# buffered-mult.net
KiCad netlist of a schematic drawn in EAGLE
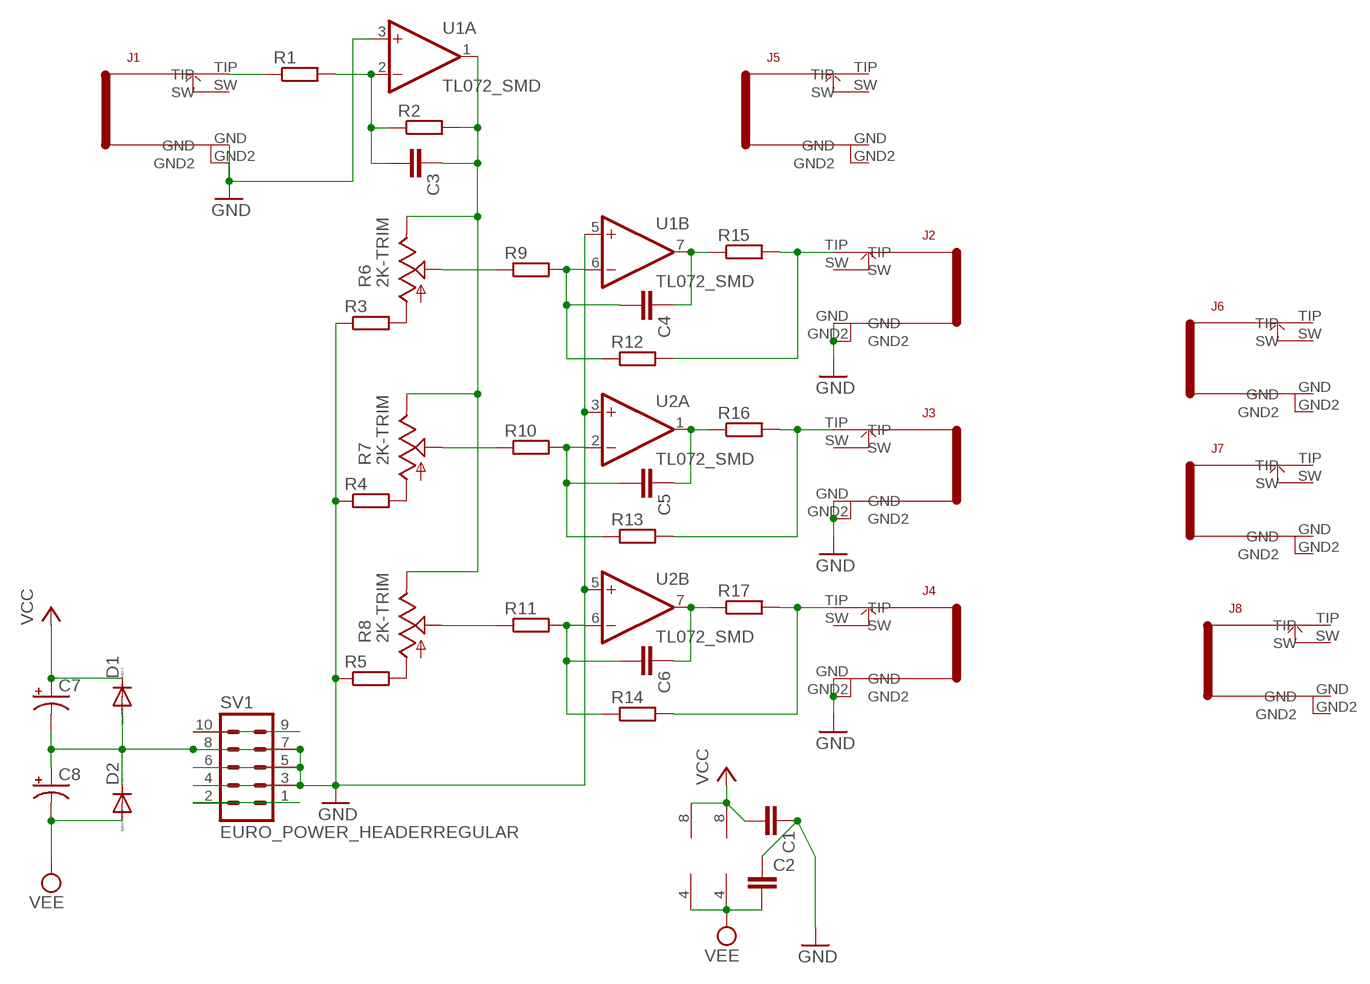
[diagram p0: schematic, sheet 1]

(export (version "E")
  (design (tool "Eeschema 10.0.6"))
  (components
    (comp (ref "C1")
      (value "C-EUC0603")
      (footprint "eagle-import:C0603")
      (libsource (lib "eagle-import") (part "C-EUC0603"))
    )
    (comp (ref "C2")
      (value "C-EUC0603")
      (footprint "eagle-import:C0603")
      (libsource (lib "eagle-import") (part "C-EUC0603"))
    )
    (comp (ref "C3")
      (value "C-EUC0603")
      (footprint "eagle-import:C0603")
      (libsource (lib "eagle-import") (part "C-EUC0603"))
    )
    (comp (ref "C4")
      (value "C-EUC0603")
      (footprint "eagle-import:C0603")
      (libsource (lib "eagle-import") (part "C-EUC0603"))
    )
    (comp (ref "C5")
      (value "C-EUC0603")
      (footprint "eagle-import:C0603")
      (libsource (lib "eagle-import") (part "C-EUC0603"))
    )
    (comp (ref "C6")
      (value "C-EUC0603")
      (footprint "eagle-import:C0603")
      (libsource (lib "eagle-import") (part "C-EUC0603"))
    )
    (comp (ref "C7")
      (value "CPOL-USD")
      (footprint "eagle-import:PANASONIC_D")
      (libsource (lib "eagle-import") (part "CPOL-USD"))
    )
    (comp (ref "C8")
      (value "CPOL-USD")
      (footprint "eagle-import:PANASONIC_D")
      (libsource (lib "eagle-import") (part "CPOL-USD"))
    )
    (comp (ref "D1")
      (value "DIODE-SOD123")
      (footprint "eagle-import:SOD123")
      (libsource (lib "eagle-import") (part "DIODE-SOD123"))
    )
    (comp (ref "D2")
      (value "DIODE-SOD123")
      (footprint "eagle-import:SOD123")
      (libsource (lib "eagle-import") (part "DIODE-SOD123"))
    )
    (comp (ref "J1")
      (value "WQP_PJ_301BM")
      (footprint "eagle-import:WQP_PJ_301BM")
      (libsource (lib "eagle-import") (part "WQP_PJ_301BM"))
    )
    (comp (ref "J2")
      (value "WQP_PJ_301BM")
      (footprint "eagle-import:WQP_PJ_301BM")
      (libsource (lib "eagle-import") (part "WQP_PJ_301BM"))
    )
    (comp (ref "J3")
      (value "WQP_PJ_301BM")
      (footprint "eagle-import:WQP_PJ_301BM")
      (libsource (lib "eagle-import") (part "WQP_PJ_301BM"))
    )
    (comp (ref "J4")
      (value "WQP_PJ_301BM")
      (footprint "eagle-import:WQP_PJ_301BM")
      (libsource (lib "eagle-import") (part "WQP_PJ_301BM"))
    )
    (comp (ref "J5")
      (value "WQP_PJ_301BM")
      (footprint "eagle-import:WQP_PJ_301BM")
      (libsource (lib "eagle-import") (part "WQP_PJ_301BM"))
    )
    (comp (ref "J6")
      (value "WQP_PJ_301BM")
      (footprint "eagle-import:WQP_PJ_301BM")
      (libsource (lib "eagle-import") (part "WQP_PJ_301BM"))
    )
    (comp (ref "J7")
      (value "WQP_PJ_301BM")
      (footprint "eagle-import:WQP_PJ_301BM")
      (libsource (lib "eagle-import") (part "WQP_PJ_301BM"))
    )
    (comp (ref "J8")
      (value "WQP_PJ_301BM")
      (footprint "eagle-import:WQP_PJ_301BM")
      (libsource (lib "eagle-import") (part "WQP_PJ_301BM"))
    )
    (comp (ref "R1")
      (value "R-EU_R0603")
      (footprint "eagle-import:R0603")
      (libsource (lib "eagle-import") (part "R-EU_R0603"))
    )
    (comp (ref "R2")
      (value "R-EU_R0603")
      (footprint "eagle-import:R0603")
      (libsource (lib "eagle-import") (part "R-EU_R0603"))
    )
    (comp (ref "R3")
      (value "R-EU_R0603")
      (footprint "eagle-import:R0603")
      (libsource (lib "eagle-import") (part "R-EU_R0603"))
    )
    (comp (ref "R4")
      (value "R-EU_R0603")
      (footprint "eagle-import:R0603")
      (libsource (lib "eagle-import") (part "R-EU_R0603"))
    )
    (comp (ref "R5")
      (value "R-EU_R0603")
      (footprint "eagle-import:R0603")
      (libsource (lib "eagle-import") (part "R-EU_R0603"))
    )
    (comp (ref "R6")
      (value "2K-TRIM")
      (footprint "eagle-import:BOURNS_TRIM_3303X3_SMD")
      (libsource (lib "eagle-import") (part "BOURNS_TRIM_3303X3_SMD"))
    )
    (comp (ref "R7")
      (value "2K-TRIM")
      (footprint "eagle-import:BOURNS_TRIM_3303X3_SMD")
      (libsource (lib "eagle-import") (part "BOURNS_TRIM_3303X3_SMD"))
    )
    (comp (ref "R8")
      (value "2K-TRIM")
      (footprint "eagle-import:BOURNS_TRIM_3303X3_SMD")
      (libsource (lib "eagle-import") (part "BOURNS_TRIM_3303X3_SMD"))
    )
    (comp (ref "R9")
      (value "R-EU_R0603")
      (footprint "eagle-import:R0603")
      (libsource (lib "eagle-import") (part "R-EU_R0603"))
    )
    (comp (ref "R10")
      (value "R-EU_R0603")
      (footprint "eagle-import:R0603")
      (libsource (lib "eagle-import") (part "R-EU_R0603"))
    )
    (comp (ref "R11")
      (value "R-EU_R0603")
      (footprint "eagle-import:R0603")
      (libsource (lib "eagle-import") (part "R-EU_R0603"))
    )
    (comp (ref "R12")
      (value "R-EU_R0603")
      (footprint "eagle-import:R0603")
      (libsource (lib "eagle-import") (part "R-EU_R0603"))
    )
    (comp (ref "R13")
      (value "R-EU_R0603")
      (footprint "eagle-import:R0603")
      (libsource (lib "eagle-import") (part "R-EU_R0603"))
    )
    (comp (ref "R14")
      (value "R-EU_R0603")
      (footprint "eagle-import:R0603")
      (libsource (lib "eagle-import") (part "R-EU_R0603"))
    )
    (comp (ref "R15")
      (value "R-EU_R0603")
      (footprint "eagle-import:R0603")
      (libsource (lib "eagle-import") (part "R-EU_R0603"))
    )
    (comp (ref "R16")
      (value "R-EU_R0603")
      (footprint "eagle-import:R0603")
      (libsource (lib "eagle-import") (part "R-EU_R0603"))
    )
    (comp (ref "R17")
      (value "R-EU_R0603")
      (footprint "eagle-import:R0603")
      (libsource (lib "eagle-import") (part "R-EU_R0603"))
    )
    (comp (ref "SV1")
      (value "EURO_POWER_HEADERREGULAR")
      (footprint "eagle-import:EURO_POWER_HEADER")
      (libsource (lib "eagle-import") (part "EURO_POWER_HEADERREGULAR"))
    )
    (comp (ref "U1")
      (value "TL072_SMD")
      (footprint "eagle-import:SO08")
      (libsource (lib "eagle-import") (part "TL072_SMD"))
    )
    (comp (ref "U2")
      (value "TL072_SMD")
      (footprint "eagle-import:SO08")
      (libsource (lib "eagle-import") (part "TL072_SMD"))
    )
  )
  (nets
    (net (code "1") (name "GND") (class "Default")
      (node (ref "C1") (pin "1") (pinfunction "1_1") (pintype "passive"))
      (node (ref "C2") (pin "1") (pinfunction "1_1") (pintype "passive"))
      (node (ref "C7") (pin "-") (pinfunction "-_-") (pintype "passive"))
      (node (ref "C8") (pin "+") (pinfunction "+_+") (pintype "passive"))
      (node (ref "D1") (pin "A") (pinfunction "A_A") (pintype "passive"))
      (node (ref "D2") (pin "C") (pinfunction "C_C") (pintype "passive"))
      (node (ref "J1") (pin "GND") (pinfunction "GND_GND") (pintype "passive"))
      (node (ref "J1") (pin "GND2") (pinfunction "GND2_GND2") (pintype "passive"))
      (node (ref "J2") (pin "GND") (pinfunction "GND_GND") (pintype "passive"))
      (node (ref "J2") (pin "GND2") (pinfunction "GND2_GND2") (pintype "passive"))
      (node (ref "J3") (pin "GND") (pinfunction "GND_GND") (pintype "passive"))
      (node (ref "J3") (pin "GND2") (pinfunction "GND2_GND2") (pintype "passive"))
      (node (ref "J4") (pin "GND") (pinfunction "GND_GND") (pintype "passive"))
      (node (ref "J4") (pin "GND2") (pinfunction "GND2_GND2") (pintype "passive"))
      (node (ref "R3") (pin "1") (pinfunction "1_1") (pintype "passive"))
      (node (ref "R4") (pin "1") (pinfunction "1_1") (pintype "passive"))
      (node (ref "R5") (pin "1") (pinfunction "1_1") (pintype "passive"))
      (node (ref "SV1") (pin "3") (pinfunction "3_3") (pintype "passive"))
      (node (ref "SV1") (pin "4") (pinfunction "4_4") (pintype "passive"))
      (node (ref "SV1") (pin "5") (pinfunction "5_5") (pintype "passive"))
      (node (ref "SV1") (pin "6") (pinfunction "6_6") (pintype "passive"))
      (node (ref "SV1") (pin "7") (pinfunction "7_7") (pintype "passive"))
      (node (ref "SV1") (pin "8") (pinfunction "8_8") (pintype "passive"))
      (node (ref "U1") (pin "3") (pinfunction "+IN_3") (pintype "input"))
      (node (ref "U1") (pin "5") (pinfunction "+IN_5") (pintype "input"))
      (node (ref "U2") (pin "3") (pinfunction "+IN_3") (pintype "input"))
      (node (ref "U2") (pin "5") (pinfunction "+IN_5") (pintype "input"))
    )
    (net (code "2") (name "Net-(J1-PadTIP)") (class "Default")
      (node (ref "J1") (pin "TIP") (pinfunction "TIP_TIP") (pintype "passive"))
      (node (ref "R1") (pin "1") (pinfunction "1_1") (pintype "passive"))
    )
    (net (code "3") (name "Net-(J2-PadTIP)") (class "Default")
      (node (ref "J2") (pin "TIP") (pinfunction "TIP_TIP") (pintype "passive"))
      (node (ref "R12") (pin "2") (pinfunction "2_2") (pintype "passive"))
      (node (ref "R15") (pin "2") (pinfunction "2_2") (pintype "passive"))
    )
    (net (code "4") (name "Net-(J3-PadTIP)") (class "Default")
      (node (ref "J3") (pin "TIP") (pinfunction "TIP_TIP") (pintype "passive"))
      (node (ref "R13") (pin "2") (pinfunction "2_2") (pintype "passive"))
      (node (ref "R16") (pin "2") (pinfunction "2_2") (pintype "passive"))
    )
    (net (code "5") (name "Net-(J4-PadTIP)") (class "Default")
      (node (ref "J4") (pin "TIP") (pinfunction "TIP_TIP") (pintype "passive"))
      (node (ref "R14") (pin "2") (pinfunction "2_2") (pintype "passive"))
      (node (ref "R17") (pin "2") (pinfunction "2_2") (pintype "passive"))
    )
    (net (code "6") (name "Net-(R6-A)") (class "Default")
      (node (ref "R3") (pin "2") (pinfunction "2_2") (pintype "passive"))
      (node (ref "R6") (pin "3") (pinfunction "A_3") (pintype "passive"))
    )
    (net (code "7") (name "Net-(R6-E)") (class "Default")
      (node (ref "C3") (pin "1") (pinfunction "1_1") (pintype "passive"))
      (node (ref "R2") (pin "2") (pinfunction "2_2") (pintype "passive"))
      (node (ref "R6") (pin "1") (pinfunction "E_1") (pintype "passive"))
      (node (ref "R7") (pin "1") (pinfunction "E_1") (pintype "passive"))
      (node (ref "R8") (pin "1") (pinfunction "E_1") (pintype "passive"))
      (node (ref "U1") (pin "1") (pinfunction "OUT_1") (pintype "output"))
    )
    (net (code "8") (name "Net-(R6-S)") (class "Default")
      (node (ref "R6") (pin "2") (pinfunction "S_2") (pintype "passive"))
      (node (ref "R9") (pin "1") (pinfunction "1_1") (pintype "passive"))
    )
    (net (code "9") (name "Net-(R7-A)") (class "Default")
      (node (ref "R4") (pin "2") (pinfunction "2_2") (pintype "passive"))
      (node (ref "R7") (pin "3") (pinfunction "A_3") (pintype "passive"))
    )
    (net (code "10") (name "Net-(R7-S)") (class "Default")
      (node (ref "R10") (pin "1") (pinfunction "1_1") (pintype "passive"))
      (node (ref "R7") (pin "2") (pinfunction "S_2") (pintype "passive"))
    )
    (net (code "11") (name "Net-(R8-A)") (class "Default")
      (node (ref "R5") (pin "2") (pinfunction "2_2") (pintype "passive"))
      (node (ref "R8") (pin "3") (pinfunction "A_3") (pintype "passive"))
    )
    (net (code "12") (name "Net-(R8-S)") (class "Default")
      (node (ref "R11") (pin "1") (pinfunction "1_1") (pintype "passive"))
      (node (ref "R8") (pin "2") (pinfunction "S_2") (pintype "passive"))
    )
    (net (code "13") (name "Net-(SV1-Pad1)") (class "Default")
      (node (ref "SV1") (pin "1") (pinfunction "1_1") (pintype "passive"))
      (node (ref "SV1") (pin "2") (pinfunction "2_2") (pintype "passive"))
    )
    (net (code "14") (name "Net-(SV1-Pad10)") (class "Default")
      (node (ref "SV1") (pin "10") (pinfunction "10_10") (pintype "passive"))
      (node (ref "SV1") (pin "9") (pinfunction "9_9") (pintype "passive"))
    )
    (net (code "15") (name "Net-(U1A--IN)") (class "Default")
      (node (ref "C3") (pin "2") (pinfunction "2_2") (pintype "passive"))
      (node (ref "R1") (pin "2") (pinfunction "2_2") (pintype "passive"))
      (node (ref "R2") (pin "1") (pinfunction "1_1") (pintype "passive"))
      (node (ref "U1") (pin "2") (pinfunction "-IN_2") (pintype "input"))
    )
    (net (code "16") (name "Net-(U1B--IN)") (class "Default")
      (node (ref "C4") (pin "2") (pinfunction "2_2") (pintype "passive"))
      (node (ref "R12") (pin "1") (pinfunction "1_1") (pintype "passive"))
      (node (ref "R9") (pin "2") (pinfunction "2_2") (pintype "passive"))
      (node (ref "U1") (pin "6") (pinfunction "-IN_6") (pintype "input"))
    )
    (net (code "17") (name "Net-(U1B-OUT)") (class "Default")
      (node (ref "C4") (pin "1") (pinfunction "1_1") (pintype "passive"))
      (node (ref "R15") (pin "1") (pinfunction "1_1") (pintype "passive"))
      (node (ref "U1") (pin "7") (pinfunction "OUT_7") (pintype "output"))
    )
    (net (code "18") (name "Net-(U2A--IN)") (class "Default")
      (node (ref "C5") (pin "2") (pinfunction "2_2") (pintype "passive"))
      (node (ref "R10") (pin "2") (pinfunction "2_2") (pintype "passive"))
      (node (ref "R13") (pin "1") (pinfunction "1_1") (pintype "passive"))
      (node (ref "U2") (pin "2") (pinfunction "-IN_2") (pintype "input"))
    )
    (net (code "19") (name "Net-(U2A-OUT)") (class "Default")
      (node (ref "C5") (pin "1") (pinfunction "1_1") (pintype "passive"))
      (node (ref "R16") (pin "1") (pinfunction "1_1") (pintype "passive"))
      (node (ref "U2") (pin "1") (pinfunction "OUT_1") (pintype "output"))
    )
    (net (code "20") (name "Net-(U2B--IN)") (class "Default")
      (node (ref "C6") (pin "2") (pinfunction "2_2") (pintype "passive"))
      (node (ref "R11") (pin "2") (pinfunction "2_2") (pintype "passive"))
      (node (ref "R14") (pin "1") (pinfunction "1_1") (pintype "passive"))
      (node (ref "U2") (pin "6") (pinfunction "-IN_6") (pintype "input"))
    )
    (net (code "21") (name "Net-(U2B-OUT)") (class "Default")
      (node (ref "C6") (pin "1") (pinfunction "1_1") (pintype "passive"))
      (node (ref "R17") (pin "1") (pinfunction "1_1") (pintype "passive"))
      (node (ref "U2") (pin "7") (pinfunction "OUT_7") (pintype "output"))
    )
    (net (code "22") (name "VCC") (class "Default")
      (node (ref "C1") (pin "2") (pinfunction "2_2") (pintype "passive"))
      (node (ref "C7") (pin "+") (pinfunction "+_+") (pintype "passive"))
      (node (ref "D1") (pin "C") (pinfunction "C_C") (pintype "passive"))
      (node (ref "U1") (pin "8") (pinfunction "V+_8") (pintype "power_in"))
      (node (ref "U2") (pin "8") (pinfunction "V+_8") (pintype "power_in"))
    )
    (net (code "23") (name "VEE") (class "Default")
      (node (ref "C2") (pin "2") (pinfunction "2_2") (pintype "passive"))
      (node (ref "C8") (pin "-") (pinfunction "-_-") (pintype "passive"))
      (node (ref "D2") (pin "A") (pinfunction "A_A") (pintype "passive"))
      (node (ref "U1") (pin "4") (pinfunction "V-_4") (pintype "power_in"))
      (node (ref "U2") (pin "4") (pinfunction "V-_4") (pintype "power_in"))
    )
    (net (code "24") (name "unconnected-(J1-PadSW)") (class "Default")
      (node (ref "J1") (pin "SW") (pinfunction "SW_SW") (pintype "passive"))
    )
    (net (code "25") (name "unconnected-(J2-PadSW)") (class "Default")
      (node (ref "J2") (pin "SW") (pinfunction "SW_SW") (pintype "passive"))
    )
    (net (code "26") (name "unconnected-(J3-PadSW)") (class "Default")
      (node (ref "J3") (pin "SW") (pinfunction "SW_SW") (pintype "passive"))
    )
    (net (code "27") (name "unconnected-(J4-PadSW)") (class "Default")
      (node (ref "J4") (pin "SW") (pinfunction "SW_SW") (pintype "passive"))
    )
    (net (code "28") (name "unconnected-(J5-PadGND)") (class "Default")
      (node (ref "J5") (pin "GND") (pinfunction "GND_GND") (pintype "passive"))
    )
    (net (code "29") (name "unconnected-(J5-PadGND2)") (class "Default")
      (node (ref "J5") (pin "GND2") (pinfunction "GND2_GND2") (pintype "passive"))
    )
    (net (code "30") (name "unconnected-(J5-PadSW)") (class "Default")
      (node (ref "J5") (pin "SW") (pinfunction "SW_SW") (pintype "passive"))
    )
    (net (code "31") (name "unconnected-(J5-PadTIP)") (class "Default")
      (node (ref "J5") (pin "TIP") (pinfunction "TIP_TIP") (pintype "passive"))
    )
    (net (code "32") (name "unconnected-(J6-PadGND)") (class "Default")
      (node (ref "J6") (pin "GND") (pinfunction "GND_GND") (pintype "passive"))
    )
    (net (code "33") (name "unconnected-(J6-PadGND2)") (class "Default")
      (node (ref "J6") (pin "GND2") (pinfunction "GND2_GND2") (pintype "passive"))
    )
    (net (code "34") (name "unconnected-(J6-PadSW)") (class "Default")
      (node (ref "J6") (pin "SW") (pinfunction "SW_SW") (pintype "passive"))
    )
    (net (code "35") (name "unconnected-(J6-PadTIP)") (class "Default")
      (node (ref "J6") (pin "TIP") (pinfunction "TIP_TIP") (pintype "passive"))
    )
    (net (code "36") (name "unconnected-(J7-PadGND)") (class "Default")
      (node (ref "J7") (pin "GND") (pinfunction "GND_GND") (pintype "passive"))
    )
    (net (code "37") (name "unconnected-(J7-PadGND2)") (class "Default")
      (node (ref "J7") (pin "GND2") (pinfunction "GND2_GND2") (pintype "passive"))
    )
    (net (code "38") (name "unconnected-(J7-PadSW)") (class "Default")
      (node (ref "J7") (pin "SW") (pinfunction "SW_SW") (pintype "passive"))
    )
    (net (code "39") (name "unconnected-(J7-PadTIP)") (class "Default")
      (node (ref "J7") (pin "TIP") (pinfunction "TIP_TIP") (pintype "passive"))
    )
    (net (code "40") (name "unconnected-(J8-PadGND)") (class "Default")
      (node (ref "J8") (pin "GND") (pinfunction "GND_GND") (pintype "passive"))
    )
    (net (code "41") (name "unconnected-(J8-PadGND2)") (class "Default")
      (node (ref "J8") (pin "GND2") (pinfunction "GND2_GND2") (pintype "passive"))
    )
    (net (code "42") (name "unconnected-(J8-PadSW)") (class "Default")
      (node (ref "J8") (pin "SW") (pinfunction "SW_SW") (pintype "passive"))
    )
    (net (code "43") (name "unconnected-(J8-PadTIP)") (class "Default")
      (node (ref "J8") (pin "TIP") (pinfunction "TIP_TIP") (pintype "passive"))
    )
  )
)
